# rx.net
KiCad netlist of a schematic drawn in EasyEDA
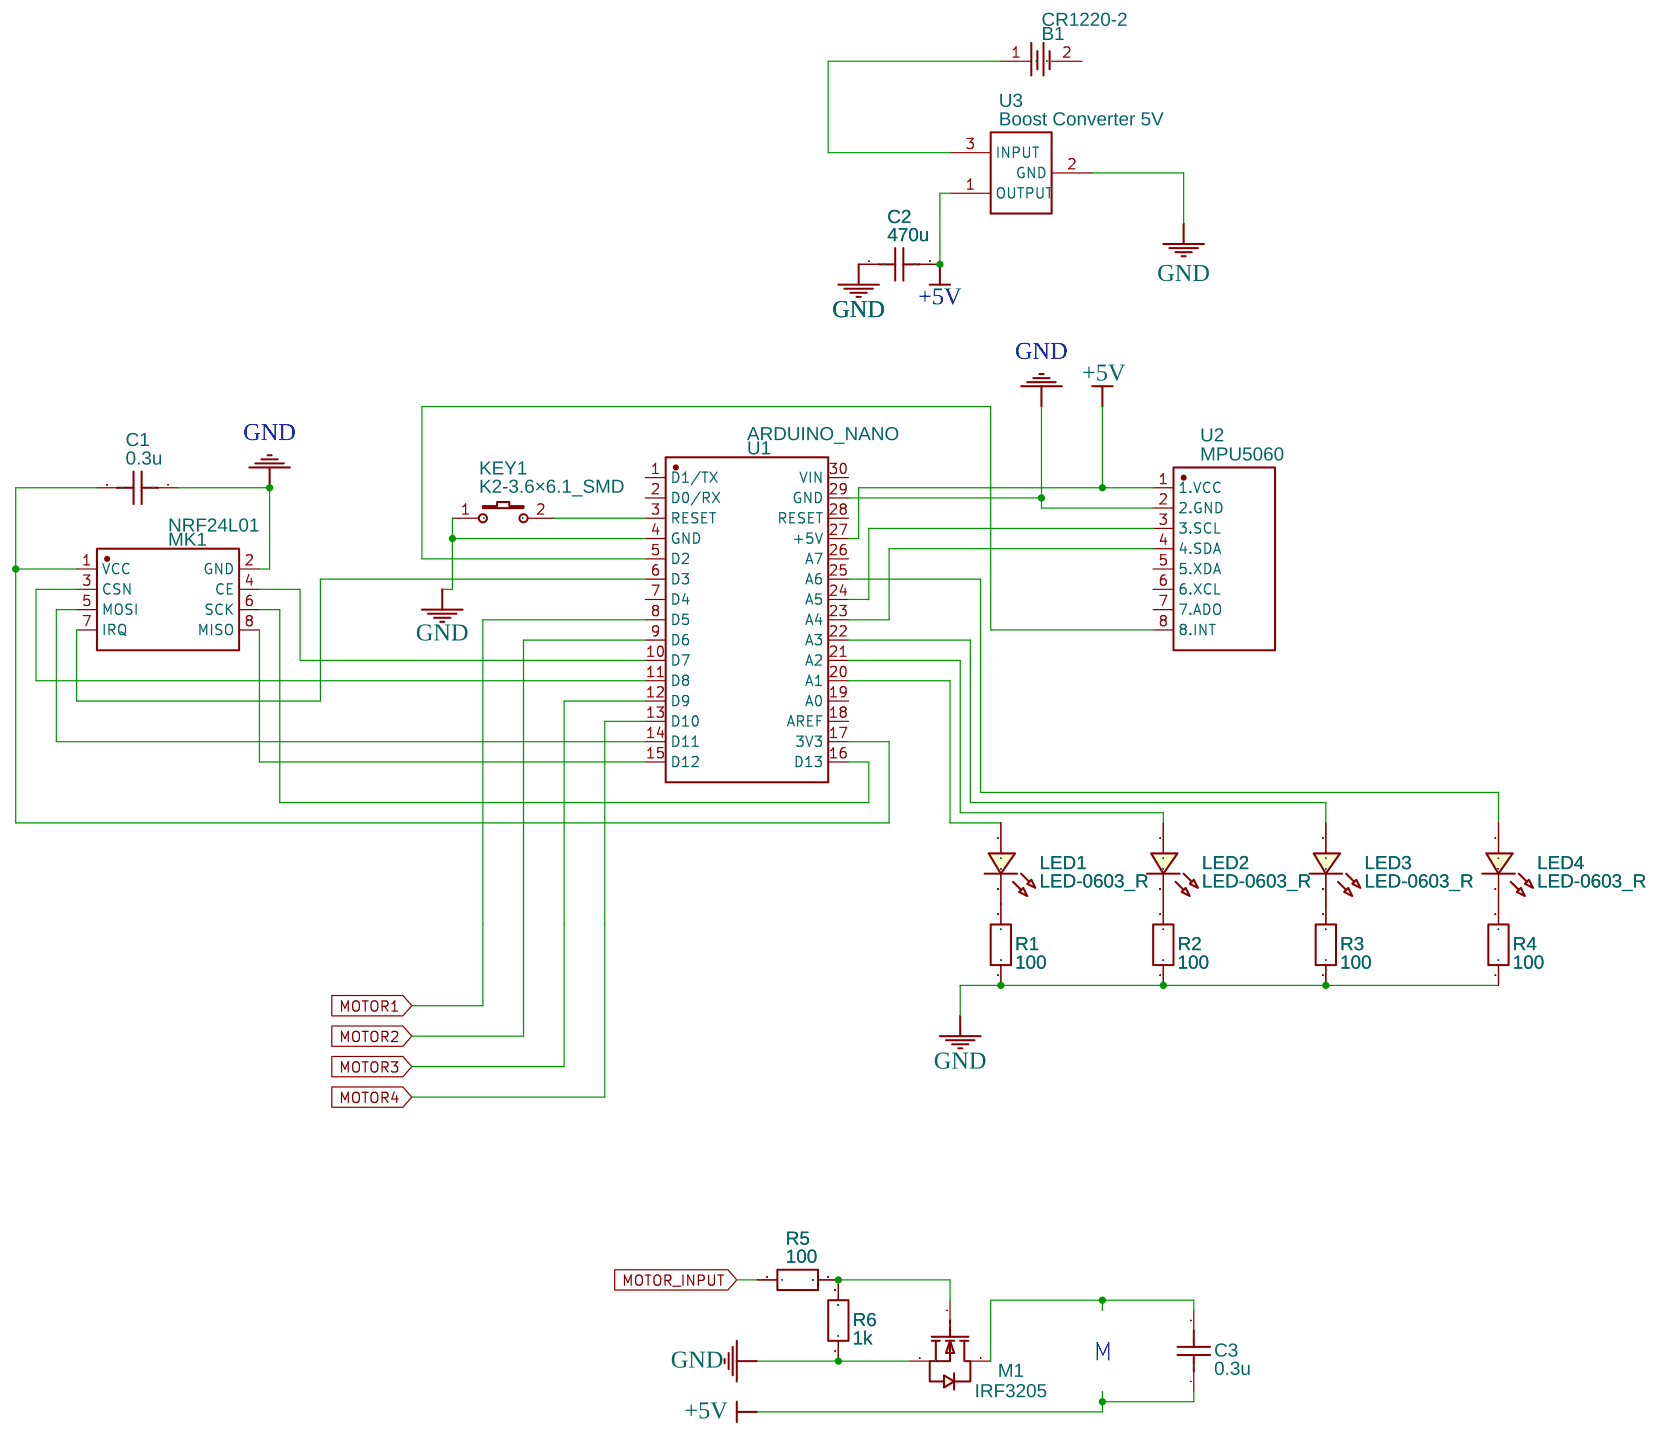
[diagram p0: schematic sheet]

(export (version "E")
  (design (tool "Eeschema 10.0.6"))
  (components
    (comp (ref "B1")
      (value "CR1220-2")
      (fields (field (name "Manufacturer") "Q&J"))
      (libsource (lib "") (part "CR1220-2"))
    )
    (comp (ref "C1") (value "0.3u") (libsource (lib "") (part "C_0603_US_1")))
    (comp (ref "C2") (value "470u") (libsource (lib "") (part "C_0603_US_2")))
    (comp (ref "C3") (value "0.3u") (libsource (lib "") (part "C_0603_US")))
    (comp (ref "KEY1")
      (value "K2-3.6×6.1_SMD")
      (fields (field (name "Manufacturer Part") "K2-1107ST-A4SW-06"))
      (libsource (lib "") (part "K2-3.6×6.1_SMD"))
    )
    (comp (ref "LED1")
      (value "LED-0603_R")
      (fields
        (field (name "Manufacturer Part") "19-217/R6C-AL1M2VY/3T")
        (field (name "Manufacturer") "EVERLIGHT(台湾亿光)")
      )
      (libsource (lib "") (part "LED-0603_R"))
    )
    (comp (ref "LED2")
      (value "LED-0603_R")
      (fields
        (field (name "Manufacturer Part") "19-217/R6C-AL1M2VY/3T")
        (field (name "Manufacturer") "EVERLIGHT(台湾亿光)")
      )
      (libsource (lib "") (part "LED-0603_R"))
    )
    (comp (ref "LED3")
      (value "LED-0603_R")
      (fields
        (field (name "Manufacturer Part") "19-217/R6C-AL1M2VY/3T")
        (field (name "Manufacturer") "EVERLIGHT(台湾亿光)")
      )
      (libsource (lib "") (part "LED-0603_R"))
    )
    (comp (ref "LED4")
      (value "LED-0603_R")
      (fields
        (field (name "Manufacturer Part") "19-217/R6C-AL1M2VY/3T")
        (field (name "Manufacturer") "EVERLIGHT(台湾亿光)")
      )
      (libsource (lib "") (part "LED-0603_R"))
    )
    (comp (ref "M1")
      (value "IRF3205")
      (fields (field (name "Manufacturer Part") "IRF3205PBF") (field (name "Manufacturer") "IR"))
      (libsource (lib "") (part "IRF3205PBF"))
    )
    (comp (ref "MK1")
      (value "NRF24L01")
      (fields (field (name "Manufacturer Part") "NF-04") (field (name "Manufacturer") "Ai-Thinker(安信可)"))
      (libsource (lib "") (part "NRF24L01"))
    )
    (comp (ref "R1") (value "100") (libsource (lib "") (part "R_0603_EU")))
    (comp (ref "R2") (value "100") (libsource (lib "") (part "R_0603_EU")))
    (comp (ref "R3") (value "100") (libsource (lib "") (part "R_0603_EU")))
    (comp (ref "R4") (value "100") (libsource (lib "") (part "R_0603_EU")))
    (comp (ref "R5") (value "100") (libsource (lib "") (part "R_0603_EU_1")))
    (comp (ref "R6") (value "1k") (libsource (lib "") (part "R_0603_EU")))
    (comp (ref "U1") (value "ARDUINO_NANO") (libsource (lib "") (part "ARDUINO_NANO")))
    (comp (ref "U2") (value "MPU5060") (libsource (lib "") (part "Ima Merlin_04171032_MPU5060")))
    (comp (ref "U3") (value "Boost Converter 5V") (libsource (lib "") (part "Boost Converter 5V")))
  )
  (nets
    (net (code "1") (name "+5V") (class "Default")
      (node (ref "C2") (pin "2") (pinfunction "2_2") (pintype "unspecified"))
      (node (ref "C3") (pin "1") (pinfunction "1_1") (pintype "unspecified"))
      (node (ref "U1") (pin "27") (pinfunction "+5V_27") (pintype "unspecified"))
      (node (ref "U2") (pin "1") (pinfunction "1.VCC_1") (pintype "unspecified"))
      (node (ref "U3") (pin "1") (pinfunction "OUTPUT_1") (pintype "unspecified"))
    )
    (net (code "2") (name "GND") (class "Default")
      (node (ref "C1") (pin "1") (pinfunction "1_1") (pintype "unspecified"))
      (node (ref "C2") (pin "1") (pinfunction "1_1") (pintype "unspecified"))
      (node (ref "KEY1") (pin "1") (pinfunction "1_1") (pintype "unspecified"))
      (node (ref "M1") (pin "3") (pinfunction "S_3") (pintype "unspecified"))
      (node (ref "MK1") (pin "2") (pinfunction "GND_2") (pintype "unspecified"))
      (node (ref "R1") (pin "1") (pinfunction "1_1") (pintype "unspecified"))
      (node (ref "R2") (pin "1") (pinfunction "1_1") (pintype "unspecified"))
      (node (ref "R3") (pin "1") (pinfunction "1_1") (pintype "unspecified"))
      (node (ref "R4") (pin "1") (pinfunction "1_1") (pintype "unspecified"))
      (node (ref "R6") (pin "1") (pinfunction "1_1") (pintype "unspecified"))
      (node (ref "U1") (pin "29") (pinfunction "GND_29") (pintype "unspecified"))
      (node (ref "U1") (pin "4") (pinfunction "GND_4") (pintype "unspecified"))
      (node (ref "U2") (pin "2") (pinfunction "2.GND_2") (pintype "unspecified"))
      (node (ref "U3") (pin "2") (pinfunction "GND_2") (pintype "unspecified"))
    )
    (net (code "3") (name "MOTOR1") (class "Default")
      (node (ref "U1") (pin "8") (pinfunction "D5_8") (pintype "unspecified"))
    )
    (net (code "4") (name "MOTOR2") (class "Default")
      (node (ref "U1") (pin "9") (pinfunction "D6_9") (pintype "unspecified"))
    )
    (net (code "5") (name "MOTOR3") (class "Default")
      (node (ref "U1") (pin "12") (pinfunction "D9_12") (pintype "unspecified"))
    )
    (net (code "6") (name "MOTOR4") (class "Default")
      (node (ref "U1") (pin "13") (pinfunction "D10_13") (pintype "unspecified"))
    )
    (net (code "7") (name "MOTOR_INPUT") (class "Default")
      (node (ref "R5") (pin "1") (pinfunction "1_1") (pintype "unspecified"))
    )
    (net (code "8") (name "Net-(KEY1-Pad2)") (class "Default")
      (node (ref "KEY1") (pin "2") (pinfunction "2_2") (pintype "unspecified"))
      (node (ref "U1") (pin "3") (pinfunction "RESET_3") (pintype "unspecified"))
    )
    (net (code "9") (name "Net-(LED1-Pad2)") (class "Default")
      (node (ref "LED1") (pin "2") (pinfunction "2_2") (pintype "unspecified"))
      (node (ref "R1") (pin "2") (pinfunction "2_2") (pintype "unspecified"))
    )
    (net (code "10") (name "Net-(LED2-Pad2)") (class "Default")
      (node (ref "LED2") (pin "2") (pinfunction "2_2") (pintype "unspecified"))
      (node (ref "R2") (pin "2") (pinfunction "2_2") (pintype "unspecified"))
    )
    (net (code "11") (name "Net-(LED3-Pad2)") (class "Default")
      (node (ref "LED3") (pin "2") (pinfunction "2_2") (pintype "unspecified"))
      (node (ref "R3") (pin "2") (pinfunction "2_2") (pintype "unspecified"))
    )
    (net (code "12") (name "Net-(LED4-Pad2)") (class "Default")
      (node (ref "LED4") (pin "2") (pinfunction "2_2") (pintype "unspecified"))
      (node (ref "R4") (pin "2") (pinfunction "2_2") (pintype "unspecified"))
    )
    (net (code "13") (name "Net-(M1-D)") (class "Default")
      (node (ref "C3") (pin "2") (pinfunction "2_2") (pintype "unspecified"))
      (node (ref "M1") (pin "2") (pinfunction "D_2") (pintype "unspecified"))
    )
    (net (code "14") (name "Net-(M1-G)") (class "Default")
      (node (ref "M1") (pin "1") (pinfunction "G_1") (pintype "unspecified"))
      (node (ref "R5") (pin "2") (pinfunction "2_2") (pintype "unspecified"))
      (node (ref "R6") (pin "2") (pinfunction "2_2") (pintype "unspecified"))
    )
    (net (code "15") (name "Net-(MK1-CE)") (class "Default")
      (node (ref "MK1") (pin "4") (pinfunction "CE_4") (pintype "unspecified"))
      (node (ref "U1") (pin "10") (pinfunction "D7_10") (pintype "unspecified"))
    )
    (net (code "16") (name "Net-(MK1-CSN)") (class "Default")
      (node (ref "MK1") (pin "3") (pinfunction "CSN_3") (pintype "unspecified"))
      (node (ref "U1") (pin "11") (pinfunction "D8_11") (pintype "unspecified"))
    )
    (net (code "17") (name "Net-(MK1-IRQ)") (class "Default")
      (node (ref "MK1") (pin "7") (pinfunction "IRQ_7") (pintype "unspecified"))
      (node (ref "U1") (pin "6") (pinfunction "D3_6") (pintype "unspecified"))
    )
    (net (code "18") (name "Net-(MK1-MISO)") (class "Default")
      (node (ref "MK1") (pin "8") (pinfunction "MISO_8") (pintype "unspecified"))
      (node (ref "U1") (pin "15") (pinfunction "D12_15") (pintype "unspecified"))
    )
    (net (code "19") (name "Net-(MK1-MOSI)") (class "Default")
      (node (ref "MK1") (pin "5") (pinfunction "MOSI_5") (pintype "unspecified"))
      (node (ref "U1") (pin "14") (pinfunction "D11_14") (pintype "unspecified"))
    )
    (net (code "20") (name "Net-(MK1-SCK)") (class "Default")
      (node (ref "MK1") (pin "6") (pinfunction "SCK_6") (pintype "unspecified"))
      (node (ref "U1") (pin "16") (pinfunction "D13_16") (pintype "unspecified"))
    )
    (net (code "21") (name "Net-(MK1-VCC)") (class "Default")
      (node (ref "C1") (pin "2") (pinfunction "2_2") (pintype "unspecified"))
      (node (ref "MK1") (pin "1") (pinfunction "VCC_1") (pintype "unspecified"))
      (node (ref "U1") (pin "17") (pinfunction "3V3_17") (pintype "unspecified"))
    )
    (net (code "22") (name "Net-(U1-A1)") (class "Default")
      (node (ref "LED1") (pin "1") (pinfunction "1_1") (pintype "unspecified"))
      (node (ref "U1") (pin "20") (pinfunction "A1_20") (pintype "unspecified"))
    )
    (net (code "23") (name "Net-(U1-A2)") (class "Default")
      (node (ref "LED2") (pin "1") (pinfunction "1_1") (pintype "unspecified"))
      (node (ref "U1") (pin "21") (pinfunction "A2_21") (pintype "unspecified"))
    )
    (net (code "24") (name "Net-(U1-A3)") (class "Default")
      (node (ref "LED3") (pin "1") (pinfunction "1_1") (pintype "unspecified"))
      (node (ref "U1") (pin "22") (pinfunction "A3_22") (pintype "unspecified"))
    )
    (net (code "25") (name "Net-(U1-A4)") (class "Default")
      (node (ref "U1") (pin "23") (pinfunction "A4_23") (pintype "unspecified"))
      (node (ref "U2") (pin "4") (pinfunction "4.SDA_4") (pintype "unspecified"))
    )
    (net (code "26") (name "Net-(U1-A5)") (class "Default")
      (node (ref "U1") (pin "24") (pinfunction "A5_24") (pintype "unspecified"))
      (node (ref "U2") (pin "3") (pinfunction "3.SCL_3") (pintype "unspecified"))
    )
    (net (code "27") (name "Net-(U1-A6)") (class "Default")
      (node (ref "LED4") (pin "1") (pinfunction "1_1") (pintype "unspecified"))
      (node (ref "U1") (pin "25") (pinfunction "A6_25") (pintype "unspecified"))
    )
    (net (code "28") (name "Net-(U1-D2)") (class "Default")
      (node (ref "U1") (pin "5") (pinfunction "D2_5") (pintype "unspecified"))
      (node (ref "U2") (pin "8") (pinfunction "8.INT_8") (pintype "unspecified"))
    )
    (net (code "29") (name "Net-(U3-INPUT)") (class "Default")
      (node (ref "B1") (pin "1") (pinfunction "1_1") (pintype "input"))
      (node (ref "U3") (pin "3") (pinfunction "INPUT_3") (pintype "unspecified"))
    )
    (net (code "30") (name "unconnected-(B1-Pad2)") (class "Default")
      (node (ref "B1") (pin "2") (pinfunction "2_2") (pintype "input"))
    )
    (net (code "31") (name "unconnected-(U1-A0-Pad19)") (class "Default")
      (node (ref "U1") (pin "19") (pinfunction "A0_19") (pintype "unspecified"))
    )
    (net (code "32") (name "unconnected-(U1-A7-Pad26)") (class "Default")
      (node (ref "U1") (pin "26") (pinfunction "A7_26") (pintype "unspecified"))
    )
    (net (code "33") (name "unconnected-(U1-AREF-Pad18)") (class "Default")
      (node (ref "U1") (pin "18") (pinfunction "AREF_18") (pintype "unspecified"))
    )
    (net (code "34") (name "unconnected-(U1-D0{slash}RX-Pad2)") (class "Default")
      (node (ref "U1") (pin "2") (pinfunction "D0/RX_2") (pintype "unspecified"))
    )
    (net (code "35") (name "unconnected-(U1-D1{slash}TX-Pad1)") (class "Default")
      (node (ref "U1") (pin "1") (pinfunction "D1/TX_1") (pintype "unspecified"))
    )
    (net (code "36") (name "unconnected-(U1-D4-Pad7)") (class "Default")
      (node (ref "U1") (pin "7") (pinfunction "D4_7") (pintype "unspecified"))
    )
    (net (code "37") (name "unconnected-(U1-RESET-Pad28)") (class "Default")
      (node (ref "U1") (pin "28") (pinfunction "RESET_28") (pintype "unspecified"))
    )
    (net (code "38") (name "unconnected-(U1-VIN-Pad30)") (class "Default")
      (node (ref "U1") (pin "30") (pinfunction "VIN_30") (pintype "unspecified"))
    )
    (net (code "39") (name "unconnected-(U2-5.XDA-Pad5)") (class "Default")
      (node (ref "U2") (pin "5") (pinfunction "5.XDA_5") (pintype "unspecified"))
    )
    (net (code "40") (name "unconnected-(U2-6.XCL-Pad6)") (class "Default")
      (node (ref "U2") (pin "6") (pinfunction "6.XCL_6") (pintype "unspecified"))
    )
    (net (code "41") (name "unconnected-(U2-7.ADO-Pad7)") (class "Default")
      (node (ref "U2") (pin "7") (pinfunction "7.ADO_7") (pintype "unspecified"))
    )
  )
)
